# MovuinoHealthBandV0_2_4-EC.net
KiCad netlist of a schematic drawn in EAGLE
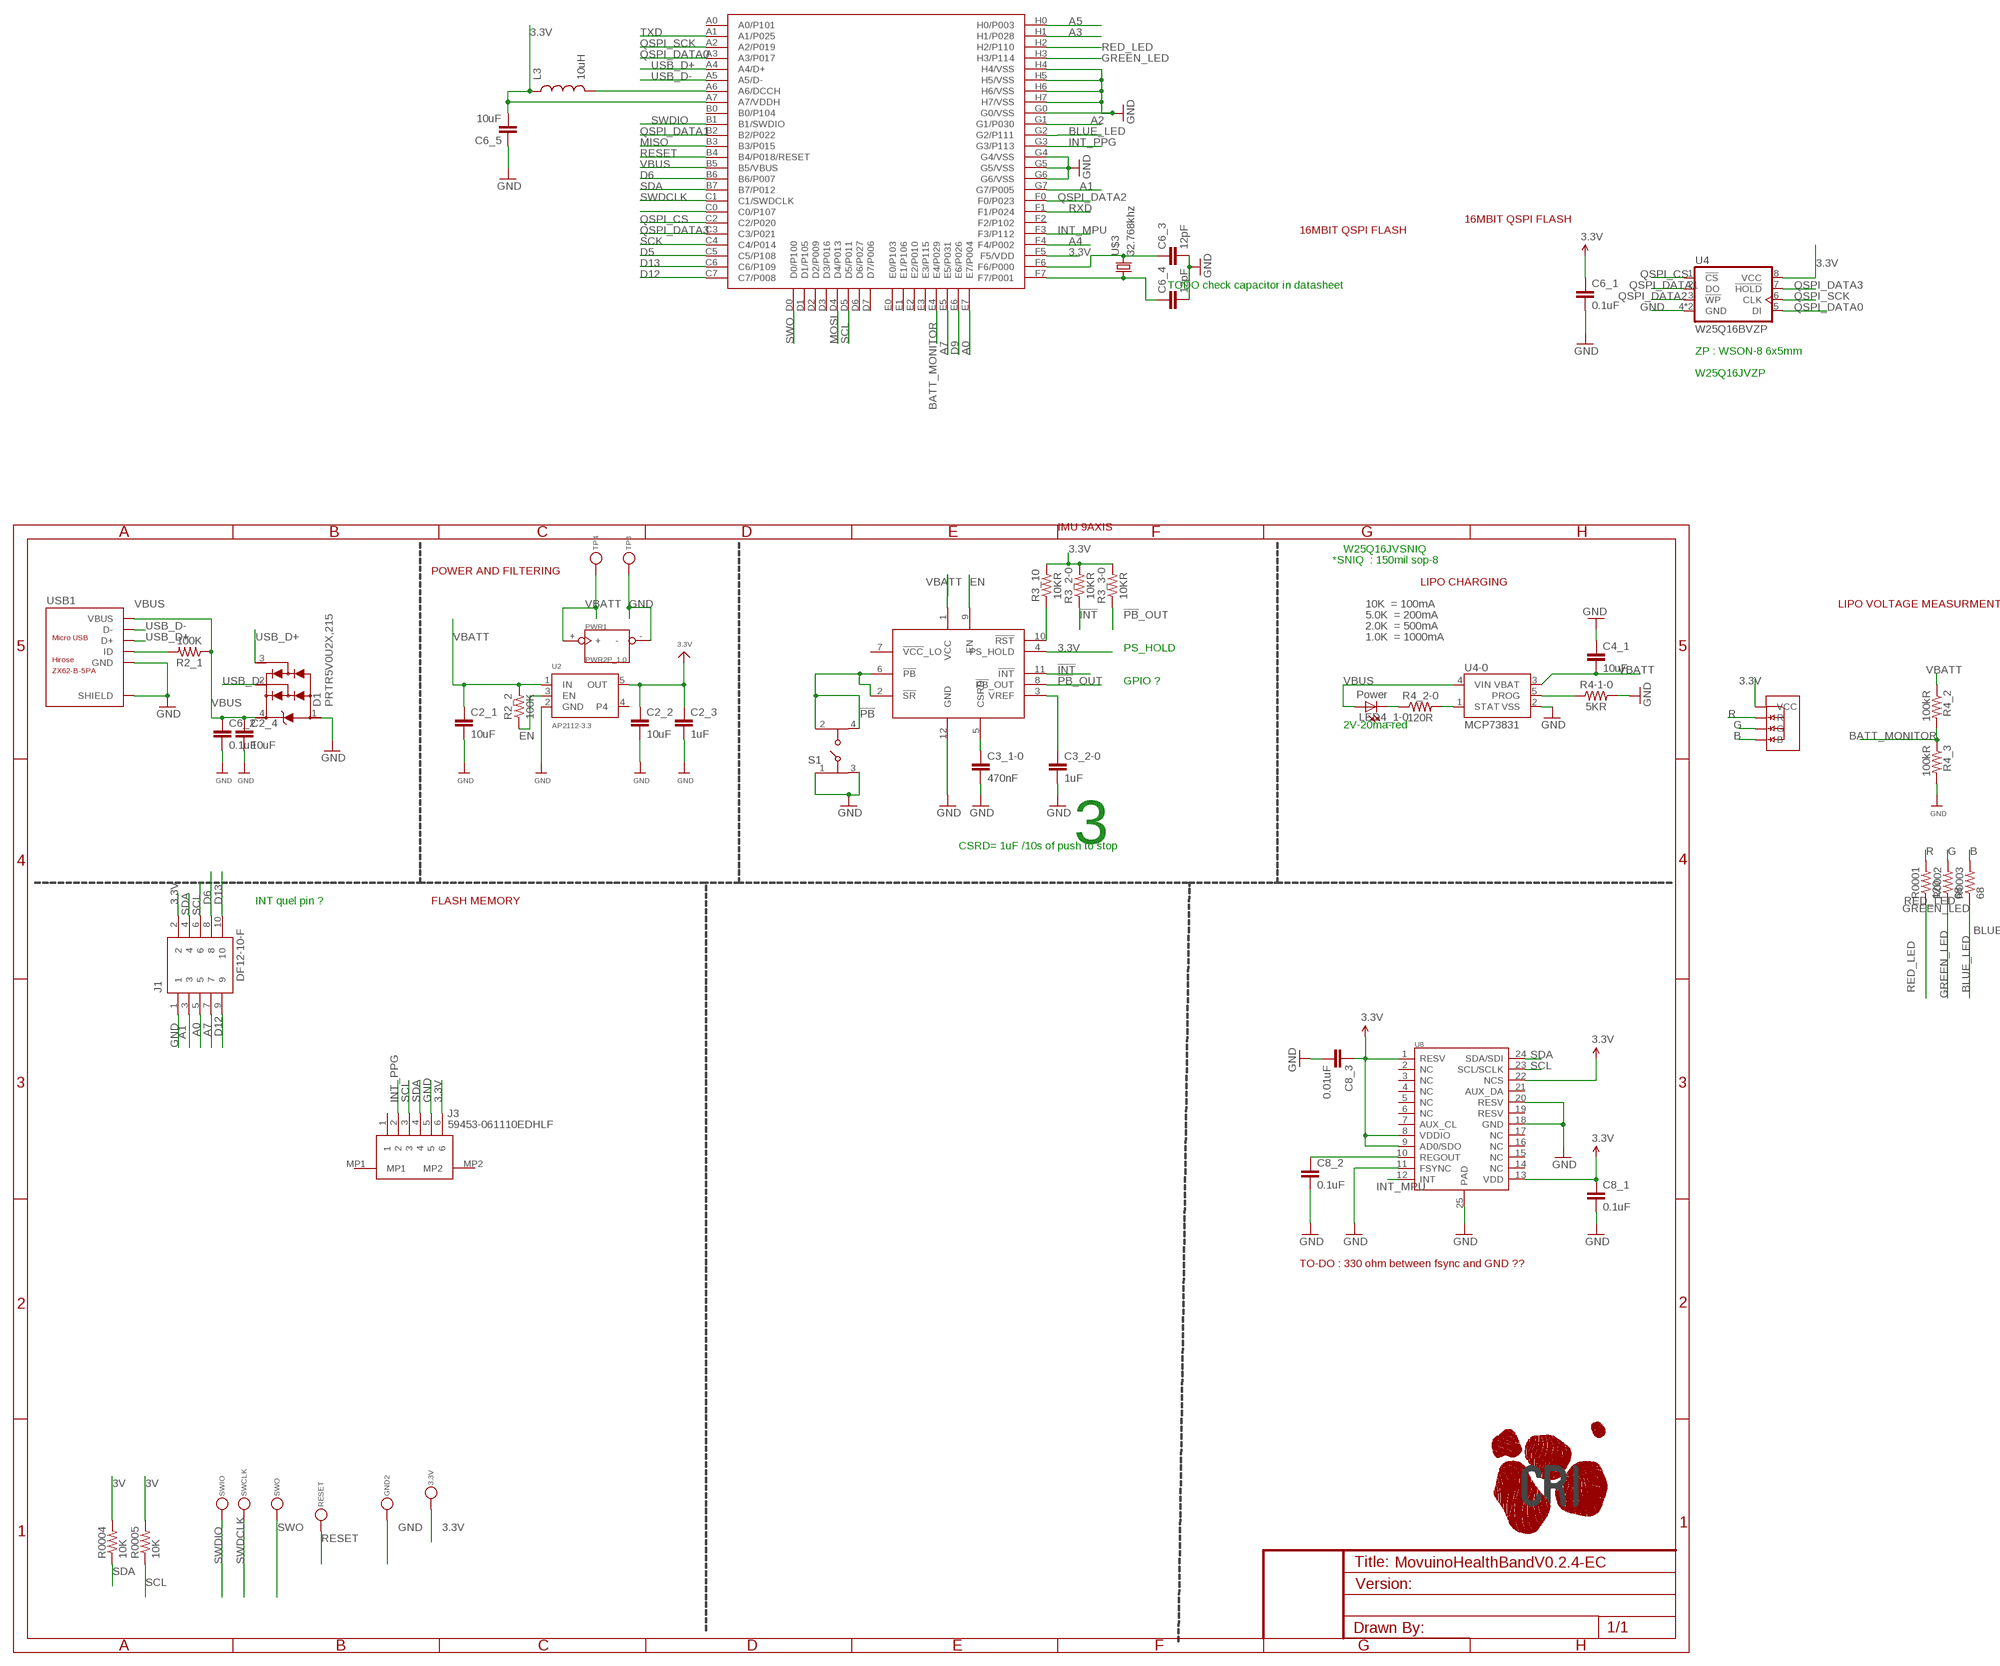
[diagram p0: schematic, sheet 1, part 1 of 2]
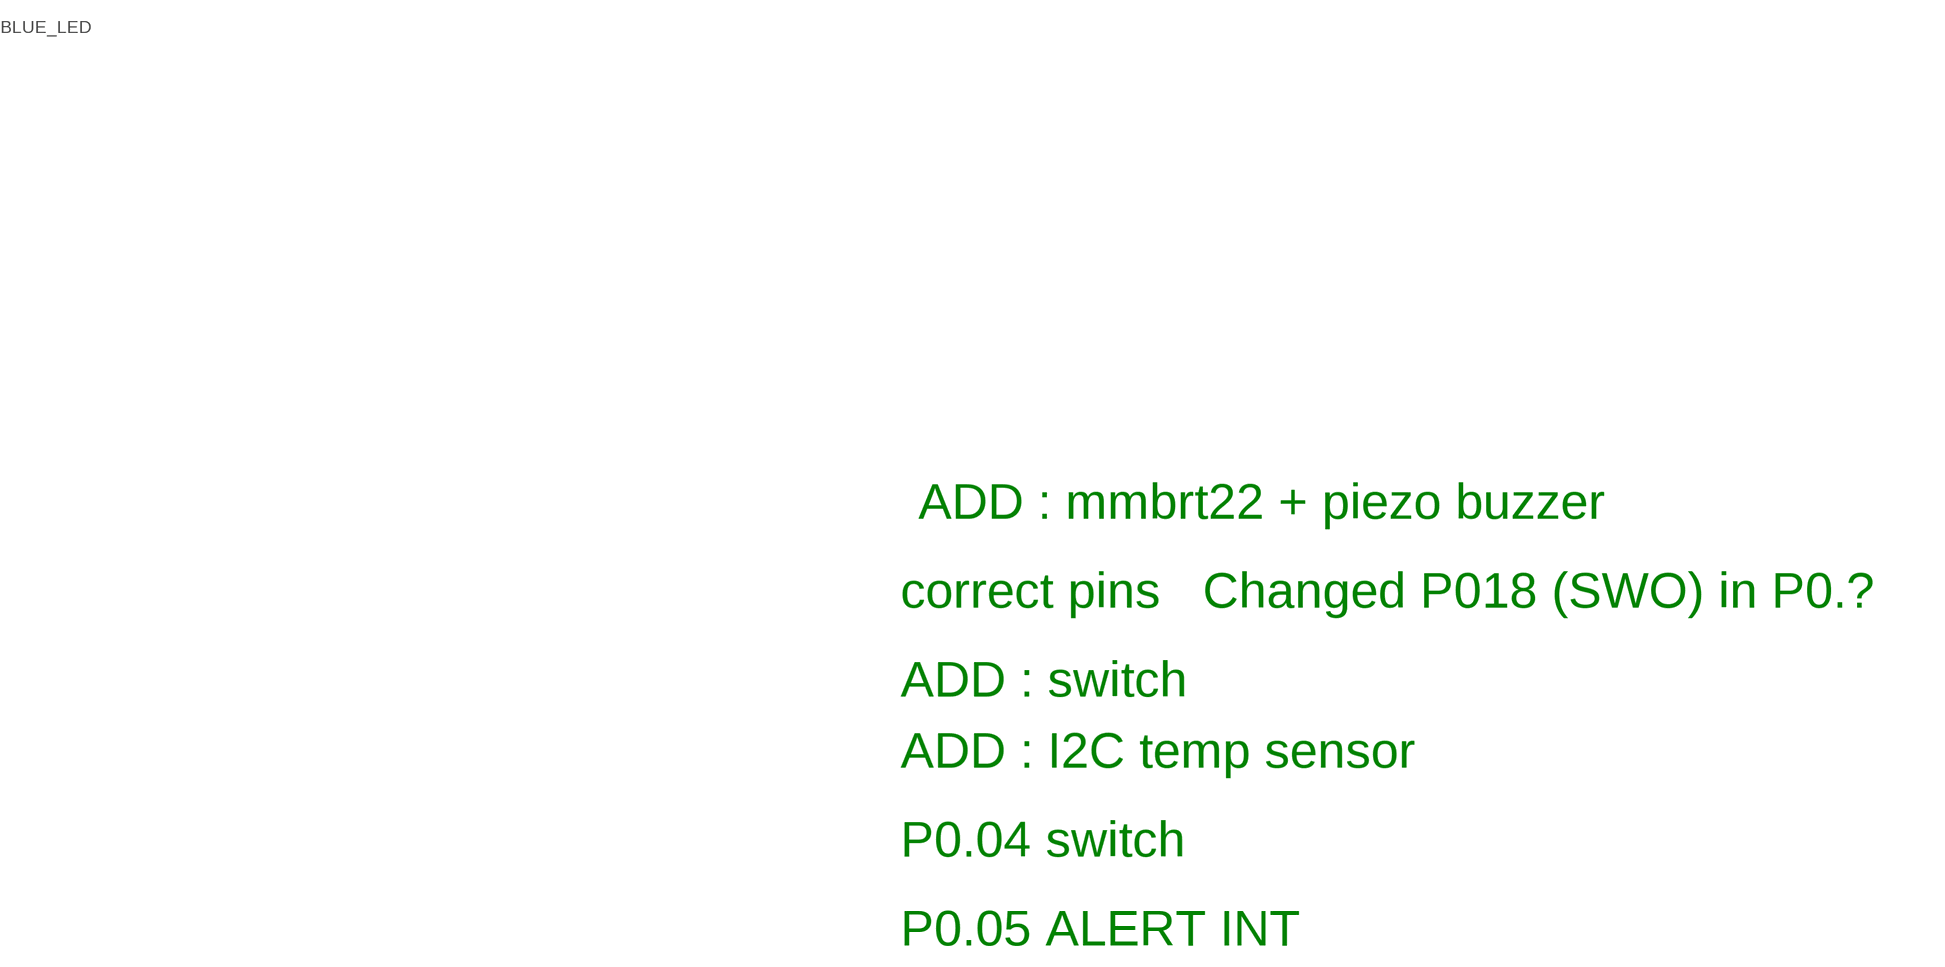
[diagram p1: schematic, sheet 1, part 2 of 2]

(export (version "E")
  (design (tool "Eeschema 10.0.6"))
  (components
    (comp (ref "3.3V")
      (value "TESTPOINTROUND1MM")
      (footprint "eagle-import:TESTPOINT_ROUND_1MM")
      (libsource (lib "eagle-import") (part "TESTPOINTROUND1MM"))
    )
    (comp (ref "C2_1")
      (value "10uF")
      (footprint "eagle-import:0402-CAP-SMALL-TDOCU")
      (libsource (lib "eagle-import") (part "CAP0402-CAP-SMALL-TDOCU"))
    )
    (comp (ref "C2_2")
      (value "10uF")
      (footprint "eagle-import:0402-CAP-SMALL-TDOCU")
      (libsource (lib "eagle-import") (part "CAP0402-CAP-SMALL-TDOCU"))
    )
    (comp (ref "C2_3")
      (value "1uF")
      (footprint "eagle-import:0402-CAP-SMALL-TDOCU")
      (libsource (lib "eagle-import") (part "CAP0402-CAP-SMALL-TDOCU"))
    )
    (comp (ref "C2_4")
      (value "10uF")
      (footprint "eagle-import:0402-CAP-SMALL-TDOCU")
      (libsource (lib "eagle-import") (part "CAP0402-CAP-SMALL-TDOCU"))
    )
    (comp (ref "C3_1-0")
      (value "470nF")
      (footprint "eagle-import:0402-CAP")
      (fields
        (field (name "MF") "Murata Electronics")
        (field (name "MPN") "GRM155R61A105KE15D")
        (field (name "TOLERANCE") "10%")
      )
      (libsource (lib "eagle-import") (part "CAP0402-1UF"))
    )
    (comp (ref "C3_2-0")
      (value "1uF")
      (footprint "eagle-import:0402-CAP")
      (fields
        (field (name "MF") "Murata Electronics")
        (field (name "MPN") "GRM155R61A105KE15D")
        (field (name "TOLERANCE") "10%")
      )
      (libsource (lib "eagle-import") (part "CAP0402-1UF"))
    )
    (comp (ref "C4_1")
      (value "10uF")
      (footprint "eagle-import:0402-CAP-SMALL-TDOCU")
      (libsource (lib "eagle-import") (part "CAP0402-CAP-SMALL-TDOCU"))
    )
    (comp (ref "C6_1")
      (value "0.1uF")
      (footprint "eagle-import:0402-CAP-SMALL-TDOCU")
      (libsource (lib "eagle-import") (part "CAP0402-CAP-SMALL-TDOCU"))
    )
    (comp (ref "C6_2")
      (value "0.1uF")
      (footprint "eagle-import:0402-CAP-SMALL-TDOCU")
      (libsource (lib "eagle-import") (part "CAP0402-CAP-SMALL-TDOCU"))
    )
    (comp (ref "C6_3")
      (value "12pF")
      (footprint "eagle-import:0402-CAP-SMALL-TDOCU")
      (libsource (lib "eagle-import") (part "CAP0402-CAP-SMALL-TDOCU"))
    )
    (comp (ref "C6_4")
      (value "12pF")
      (footprint "eagle-import:0402-CAP-SMALL-TDOCU")
      (libsource (lib "eagle-import") (part "CAP0402-CAP-SMALL-TDOCU"))
    )
    (comp (ref "C6_5")
      (value "10uF")
      (footprint "eagle-import:0402-CAP-SMALL-TDOCU")
      (libsource (lib "eagle-import") (part "CAP0402-CAP-SMALL-TDOCU"))
    )
    (comp (ref "C8_1")
      (value "0.1uF")
      (footprint "eagle-import:0402-CAP-SMALL-TDOCU")
      (libsource (lib "eagle-import") (part "CAP0402-CAP-SMALL-TDOCU"))
    )
    (comp (ref "C8_2")
      (value "0.1uF")
      (footprint "eagle-import:0402-CAP-SMALL-TDOCU")
      (libsource (lib "eagle-import") (part "CAP0402-CAP-SMALL-TDOCU"))
    )
    (comp (ref "C8_3")
      (value "0.01uF")
      (footprint "eagle-import:0402-CAP-SMALL-TDOCU")
      (libsource (lib "eagle-import") (part "CAP0402-CAP-SMALL-TDOCU"))
    )
    (comp (ref "D1")
      (value "PRTR5V0U2X,215")
      (footprint "eagle-import:SOT143B")
      (fields (field (name "MF") "Nexperia USA"))
      (libsource (lib "eagle-import") (part "PRTR5V0U2X,215"))
    )
    (comp (ref "GND2")
      (value "TESTPOINTROUND1MM")
      (footprint "eagle-import:TESTPOINT_ROUND_1MM")
      (libsource (lib "eagle-import") (part "TESTPOINTROUND1MM"))
    )
    (comp (ref "J1")
      (value "DF12-10-F")
      (footprint "eagle-import:DF12-10-DP")
      (fields (field (name "MF") "Hirose") (field (name "MPN") "DF12E(3.0)-10DP-0.5V(81)"))
      (libsource (lib "eagle-import") (part "DF12-10-F"))
    )
    (comp (ref "J3")
      (value "59453-061110EDHLF")
      (footprint "eagle-import:59453061110EDHLF")
      (libsource (lib "eagle-import") (part "59453-061110EDHLF"))
    )
    (comp (ref "L3")
      (value "10uH")
      (footprint "eagle-import:C0402")
      (libsource (lib "eagle-import") (part "INDUCTOR0402"))
    )
    (comp (ref "LED4_1-0")
      (value "Power")
      (footprint "eagle-import:LED-0603")
      (fields (field (name "MF") "OSRAM Opto Semiconductors") (field (name "MPN") "LS Q976-NR-1"))
      (libsource (lib "eagle-import") (part "LED0603-RED-STD"))
    )
    (comp (ref "PWR1")
      (value "PWR2P_1.0")
      (footprint "eagle-import:PWR2P_1.0")
      (fields (field (name "MF") "JST") (field (name "MPN") "SM02B-SRSS-TB(LFSN)"))
      (libsource (lib "eagle-import") (part "PWR2P_1.0"))
    )
    (comp (ref "R0001")
      (value "120")
      (footprint "eagle-import:0402-RES")
      (fields
        (field (name "MF") "TE Connectivity")
        (field (name "MPN") "CRG0402F10K")
        (field (name "TOLERANCE") "1%")
      )
      (libsource (lib "eagle-import") (part "RESISTOR0402-10K"))
    )
    (comp (ref "R0002")
      (value "68")
      (footprint "eagle-import:0402-RES")
      (fields
        (field (name "MF") "TE Connectivity")
        (field (name "MPN") "CRG0402F10K")
        (field (name "TOLERANCE") "1%")
      )
      (libsource (lib "eagle-import") (part "RESISTOR0402-10K"))
    )
    (comp (ref "R2_1")
      (value "100K")
      (footprint "eagle-import:R0402-SMALL-TDOCU")
      (libsource (lib "eagle-import") (part "RESISTORR0402-SMALL-TDOCU"))
    )
    (comp (ref "R2_2")
      (value "100K")
      (footprint "eagle-import:R0402-SMALL-TDOCU")
      (libsource (lib "eagle-import") (part "RESISTORR0402-SMALL-TDOCU"))
    )
    (comp (ref "R0003")
      (value "68")
      (footprint "eagle-import:0402-RES")
      (fields
        (field (name "MF") "TE Connectivity")
        (field (name "MPN") "CRG0402F10K")
        (field (name "TOLERANCE") "1%")
      )
      (libsource (lib "eagle-import") (part "RESISTOR0402-10K"))
    )
    (comp (ref "R3_2-0")
      (value "10KR")
      (footprint "eagle-import:R0402-SMALL-TDOCU")
      (libsource (lib "eagle-import") (part "RESISTORR0402-SMALL-TDOCU"))
    )
    (comp (ref "R3_3-0")
      (value "10KR")
      (footprint "eagle-import:R0402-SMALL-TDOCU")
      (libsource (lib "eagle-import") (part "RESISTORR0402-SMALL-TDOCU"))
    )
    (comp (ref "R3_10")
      (value "10KR")
      (footprint "eagle-import:R0402-SMALL-TDOCU")
      (libsource (lib "eagle-import") (part "RESISTORR0402-SMALL-TDOCU"))
    )
    (comp (ref "R0004")
      (value "10K")
      (footprint "eagle-import:0402-RES")
      (fields
        (field (name "MF") "TE Connectivity")
        (field (name "MPN") "CRG0402F10K")
        (field (name "TOLERANCE") "1%")
      )
      (libsource (lib "eagle-import") (part "RESISTOR0402-10K"))
    )
    (comp (ref "R4-1-0")
      (value "5KR")
      (footprint "eagle-import:R0402-SMALL-TDOCU")
      (libsource (lib "eagle-import") (part "RESISTORR0402-SMALL-TDOCU"))
    )
    (comp (ref "R4_2")
      (value "100kR")
      (footprint "eagle-import:0402-RES")
      (fields
        (field (name "MF") "TE Connectivity")
        (field (name "MPN") "CRG0402F10K")
        (field (name "TOLERANCE") "1%")
      )
      (libsource (lib "eagle-import") (part "RESISTOR0402-10K"))
    )
    (comp (ref "R4_2-0")
      (value "120R")
      (footprint "eagle-import:R0402-SMALL-TDOCU")
      (libsource (lib "eagle-import") (part "RESISTORR0402-SMALL-TDOCU"))
    )
    (comp (ref "R4_3")
      (value "100kR")
      (footprint "eagle-import:0402-RES")
      (fields
        (field (name "MF") "TE Connectivity")
        (field (name "MPN") "CRG0402F10K")
        (field (name "TOLERANCE") "1%")
      )
      (libsource (lib "eagle-import") (part "RESISTOR0402-10K"))
    )
    (comp (ref "R0005")
      (value "10K")
      (footprint "eagle-import:0402-RES")
      (fields
        (field (name "MF") "TE Connectivity")
        (field (name "MPN") "CRG0402F10K")
        (field (name "TOLERANCE") "1%")
      )
      (libsource (lib "eagle-import") (part "RESISTOR0402-10K"))
    )
    (comp (ref "RESET")
      (value "TESTPOINTROUND1MM")
      (footprint "eagle-import:TESTPOINT_ROUND_1MM")
      (libsource (lib "eagle-import") (part "TESTPOINTROUND1MM"))
    )
    (comp (ref "S1")
      (value "434331045822")
      (footprint "eagle-import:434331045822")
      (libsource (lib "eagle-import") (part "434331045822"))
    )
    (comp (ref "SWCLK")
      (value "TESTPOINTROUND1MM")
      (footprint "eagle-import:TESTPOINT_ROUND_1MM")
      (libsource (lib "eagle-import") (part "TESTPOINTROUND1MM"))
    )
    (comp (ref "SWIO")
      (value "TESTPOINTROUND1MM")
      (footprint "eagle-import:TESTPOINT_ROUND_1MM")
      (libsource (lib "eagle-import") (part "TESTPOINTROUND1MM"))
    )
    (comp (ref "SWO")
      (value "TESTPOINTROUND1MM")
      (footprint "eagle-import:TESTPOINT_ROUND_1MM")
      (libsource (lib "eagle-import") (part "TESTPOINTROUND1MM"))
    )
    (comp (ref "TP3")
      (value "TESTPOINT1X1.5MM_NOCREAM_NOSILK")
      (footprint "eagle-import:PAD-1X1.5_NOSILK")
      (libsource (lib "eagle-import") (part "TESTPOINT1X1.5MM_NOCREAM_NOSILK"))
    )
    (comp (ref "TP4")
      (value "TESTPOINT1X1.5MM_NOCREAM_NOSILK")
      (footprint "eagle-import:PAD-1X1.5_NOSILK")
      (libsource (lib "eagle-import") (part "TESTPOINT1X1.5MM_NOCREAM_NOSILK"))
    )
    (comp (ref "U$2")
      (value "LOGO-CRI-NEW-110MM-BOTTOM-SILK")
      (footprint "eagle-import:LOGO_CRI-NEW-BMP10MM-BOTTOM")
      (libsource (lib "eagle-import") (part "LOGO-CRI-NEW-110MM-BOTTOM-SILK"))
    )
    (comp (ref "U$3")
      (value "32.768khz")
      (footprint "eagle-import:CRYSTAL-SMD-2X1.2-ABS06")
      (libsource (lib "eagle-import") (part "CRYSTAL-NOGND"))
    )
    (comp (ref "U$24")
      (value "LRTB_R48G")
      (footprint "eagle-import:LRTB_R48G")
      (fields (field (name "MF") "Osram Opto Semiconductors") (field (name "MPN") "LRTBR48G"))
      (libsource (lib "eagle-import") (part "LRTB_R48G"))
    )
    (comp (ref "U2")
      (value "AP2112-3.3")
      (footprint "eagle-import:SOT23-5")
      (libsource (lib "eagle-import") (part "VREG_SOT23-5"))
    )
    (comp (ref "U3")
      (value "BC840")
      (footprint "eagle-import:BC840")
      (libsource (lib "eagle-import") (part "BC840"))
    )
    (comp (ref "U3-0")
      (value "STM6601")
      (footprint "eagle-import:TDFN12")
      (libsource (lib "eagle-import") (part "STM6601"))
    )
    (comp (ref "U4")
      (value "W25Q16BVZP")
      (footprint "eagle-import:WSON8")
      (libsource (lib "eagle-import") (part "W25Q16BVZP"))
    )
    (comp (ref "U4-0")
      (value "MCP73831")
      (footprint "eagle-import:SOT23-5")
      (fields (field (name "MF") "Microchip") (field (name "MPN") "MCP73831T-2ACI/OT"))
      (libsource (lib "eagle-import") (part "MCP73831"))
    )
    (comp (ref "U8")
      (value "MPU-9250")
      (footprint "eagle-import:LEAD-QFN24")
      (fields (field (name "MF") "InvenSense"))
      (libsource (lib "eagle-import") (part "MPU-9250"))
    )
    (comp (ref "USB1")
      (value "MICRO-USB-SMD(ZX62-B-5PA)TB1")
      (footprint "eagle-import:MICRO-USB5+6P-SMD-0.65-AB-TB")
      (libsource (lib "eagle-import") (part "MICRO-USB-SMD(ZX62-B-5PA)TB1"))
    )
  )
  (nets
    (net (code "1") (name "/3V") (class "Default")
      (node (ref "R0004") (pin "2") (pinfunction "2_2") (pintype "passive"))
      (node (ref "R0005") (pin "2") (pinfunction "2_2") (pintype "passive"))
    )
    (net (code "2") (name "/A0") (class "Default")
      (node (ref "J1") (pin "5") (pinfunction "5_5") (pintype "bidirectional"))
      (node (ref "U3") (pin "E7") (pinfunction "E7/P004_E7") (pintype "bidirectional"))
    )
    (net (code "3") (name "/A1") (class "Default")
      (node (ref "J1") (pin "3") (pinfunction "3_3") (pintype "bidirectional"))
      (node (ref "U3") (pin "G7") (pinfunction "G7/P005_G7") (pintype "bidirectional"))
    )
    (net (code "4") (name "/A2") (class "Default")
      (node (ref "U3") (pin "G1") (pinfunction "G1/P030_G1") (pintype "bidirectional"))
    )
    (net (code "5") (name "/A3") (class "Default")
      (node (ref "U3") (pin "H1") (pinfunction "H1/P028_H1") (pintype "bidirectional"))
    )
    (net (code "6") (name "/A4") (class "Default")
      (node (ref "U3") (pin "F4") (pinfunction "F4/P002_F4") (pintype "bidirectional"))
    )
    (net (code "7") (name "/A5") (class "Default")
      (node (ref "U3") (pin "H0") (pinfunction "H0/P003_H0") (pintype "bidirectional"))
    )
    (net (code "8") (name "/A7") (class "Default")
      (node (ref "J1") (pin "7") (pinfunction "7_7") (pintype "bidirectional"))
      (node (ref "U3") (pin "E5") (pinfunction "E5/P031_E5") (pintype "bidirectional"))
    )
    (net (code "9") (name "/B") (class "Default")
      (node (ref "R0003") (pin "2") (pinfunction "2_2") (pintype "passive"))
      (node (ref "U$24") (pin "4") (pinfunction "B_4") (pintype "bidirectional"))
    )
    (net (code "10") (name "/BATT_MONITOR") (class "Default")
      (node (ref "R4_2") (pin "2") (pinfunction "2_2") (pintype "passive"))
      (node (ref "R4_3") (pin "1") (pinfunction "1_1") (pintype "passive"))
      (node (ref "U3") (pin "E4") (pinfunction "E4/P029_E4") (pintype "bidirectional"))
    )
    (net (code "11") (name "/BLUE_LED") (class "Default")
      (node (ref "R0003") (pin "1") (pinfunction "1_1") (pintype "passive"))
      (node (ref "U3") (pin "G2") (pinfunction "G2/P111_G2") (pintype "bidirectional"))
    )
    (net (code "12") (name "/D5") (class "Default")
      (node (ref "U3") (pin "C5") (pinfunction "C5/P108_C5") (pintype "bidirectional"))
    )
    (net (code "13") (name "/D6") (class "Default")
      (node (ref "J1") (pin "8") (pinfunction "8_8") (pintype "bidirectional"))
      (node (ref "U3") (pin "B6") (pinfunction "B6/P007_B6") (pintype "bidirectional"))
    )
    (net (code "14") (name "/D9") (class "Default")
      (node (ref "U3") (pin "E6") (pinfunction "E6/P026_E6") (pintype "bidirectional"))
    )
    (net (code "15") (name "/D12") (class "Default")
      (node (ref "J1") (pin "9") (pinfunction "9_9") (pintype "bidirectional"))
      (node (ref "U3") (pin "C7") (pinfunction "C7/P008_C7") (pintype "bidirectional"))
    )
    (net (code "16") (name "/D13") (class "Default")
      (node (ref "J1") (pin "10") (pinfunction "10_10") (pintype "bidirectional"))
      (node (ref "U3") (pin "C6") (pinfunction "C6/P109_C6") (pintype "bidirectional"))
    )
    (net (code "17") (name "/EN") (class "Default")
      (node (ref "R2_2") (pin "1") (pinfunction "1_1") (pintype "passive"))
      (node (ref "U2") (pin "3") (pinfunction "EN_3") (pintype "input"))
      (node (ref "U3-0") (pin "9") (pinfunction "EN_9") (pintype "output"))
    )
    (net (code "18") (name "/G") (class "Default")
      (node (ref "R0002") (pin "2") (pinfunction "2_2") (pintype "passive"))
      (node (ref "U$24") (pin "3") (pinfunction "G_3") (pintype "bidirectional"))
    )
    (net (code "19") (name "/GREEN_LED") (class "Default")
      (node (ref "R0002") (pin "1") (pinfunction "1_1") (pintype "passive"))
      (node (ref "U3") (pin "H3") (pinfunction "H3/P114_H3") (pintype "bidirectional"))
    )
    (net (code "20") (name "/INT_MPU") (class "Default")
      (node (ref "U3") (pin "F3") (pinfunction "F3/P112_F3") (pintype "bidirectional"))
      (node (ref "U8") (pin "12") (pinfunction "INT_12") (pintype "bidirectional"))
    )
    (net (code "21") (name "/INT_PPG") (class "Default")
      (node (ref "J3") (pin "2") (pinfunction "2_2") (pintype "bidirectional"))
      (node (ref "U3") (pin "G3") (pinfunction "G3/P113_G3") (pintype "bidirectional"))
    )
    (net (code "22") (name "/MISO") (class "Default")
      (node (ref "U3") (pin "B3") (pinfunction "B3/P015_B3") (pintype "bidirectional"))
    )
    (net (code "23") (name "/MOSI") (class "Default")
      (node (ref "U3") (pin "D4") (pinfunction "D4/P013_D4") (pintype "bidirectional"))
    )
    (net (code "24") (name "/QSPI_CS") (class "Default")
      (node (ref "U3") (pin "C2") (pinfunction "C2/P020_C2") (pintype "bidirectional"))
      (node (ref "U4") (pin "1") (pinfunction "~{CS}_1") (pintype "input"))
    )
    (net (code "25") (name "/QSPI_DATA0") (class "Default")
      (node (ref "U3") (pin "A3") (pinfunction "A3/P017_A3") (pintype "bidirectional"))
      (node (ref "U4") (pin "5") (pinfunction "DI_5") (pintype "input"))
    )
    (net (code "26") (name "/QSPI_DATA1") (class "Default")
      (node (ref "U3") (pin "B2") (pinfunction "B2/P022_B2") (pintype "bidirectional"))
      (node (ref "U4") (pin "2") (pinfunction "DO_2") (pintype "output"))
    )
    (net (code "27") (name "/QSPI_DATA2") (class "Default")
      (node (ref "U3") (pin "F0") (pinfunction "F0/P023_F0") (pintype "bidirectional"))
      (node (ref "U4") (pin "3") (pinfunction "~{WP}_3") (pintype "input"))
    )
    (net (code "28") (name "/QSPI_DATA3") (class "Default")
      (node (ref "U3") (pin "C3") (pinfunction "C3/P021_C3") (pintype "bidirectional"))
      (node (ref "U4") (pin "7") (pinfunction "~{HOLD}_7") (pintype "input"))
    )
    (net (code "29") (name "/QSPI_SCK") (class "Default")
      (node (ref "U3") (pin "A2") (pinfunction "A2/P019_A2") (pintype "bidirectional"))
      (node (ref "U4") (pin "6") (pinfunction "CLK_6") (pintype "input"))
    )
    (net (code "30") (name "/R") (class "Default")
      (node (ref "R0001") (pin "2") (pinfunction "2_2") (pintype "passive"))
      (node (ref "U$24") (pin "2") (pinfunction "R_2") (pintype "bidirectional"))
    )
    (net (code "31") (name "/RED_LED") (class "Default")
      (node (ref "R0001") (pin "1") (pinfunction "1_1") (pintype "passive"))
      (node (ref "U3") (pin "H2") (pinfunction "H2/P110_H2") (pintype "bidirectional"))
    )
    (net (code "32") (name "/RESET") (class "Default")
      (node (ref "RESET") (pin "P$1") (pinfunction "P$1_P$1") (pintype "bidirectional"))
      (node (ref "U3") (pin "B4") (pinfunction "B4/P018/RESET_B4") (pintype "bidirectional"))
    )
    (net (code "33") (name "/RXD") (class "Default")
      (node (ref "U3") (pin "F1") (pinfunction "F1/P024_F1") (pintype "bidirectional"))
    )
    (net (code "34") (name "/SCK") (class "Default")
      (node (ref "U3") (pin "C4") (pinfunction "C4/P014_C4") (pintype "bidirectional"))
    )
    (net (code "35") (name "/SCL") (class "Default")
      (node (ref "J1") (pin "6") (pinfunction "6_6") (pintype "bidirectional"))
      (node (ref "J3") (pin "3") (pinfunction "3_3") (pintype "bidirectional"))
      (node (ref "R0005") (pin "1") (pinfunction "1_1") (pintype "passive"))
      (node (ref "U3") (pin "D5") (pinfunction "D5/P011_D5") (pintype "bidirectional"))
      (node (ref "U8") (pin "23") (pinfunction "SCL/SCLK_23") (pintype "bidirectional"))
    )
    (net (code "36") (name "/SDA") (class "Default")
      (node (ref "J1") (pin "4") (pinfunction "4_4") (pintype "bidirectional"))
      (node (ref "J3") (pin "4") (pinfunction "4_4") (pintype "bidirectional"))
      (node (ref "R0004") (pin "1") (pinfunction "1_1") (pintype "passive"))
      (node (ref "U3") (pin "B7") (pinfunction "B7/P012_B7") (pintype "bidirectional"))
      (node (ref "U8") (pin "24") (pinfunction "SDA/SDI_24") (pintype "bidirectional"))
    )
    (net (code "37") (name "/SWDCLK") (class "Default")
      (node (ref "SWCLK") (pin "P$1") (pinfunction "P$1_P$1") (pintype "bidirectional"))
      (node (ref "U3") (pin "C1") (pinfunction "C1/SWDCLK_C1") (pintype "bidirectional"))
    )
    (net (code "38") (name "/SWDIO") (class "Default")
      (node (ref "SWIO") (pin "P$1") (pinfunction "P$1_P$1") (pintype "bidirectional"))
      (node (ref "U3") (pin "B1") (pinfunction "B1/SWDIO_B1") (pintype "bidirectional"))
    )
    (net (code "39") (name "/SWO") (class "Default")
      (node (ref "SWO") (pin "P$1") (pinfunction "P$1_P$1") (pintype "bidirectional"))
      (node (ref "U3") (pin "D0") (pinfunction "D0/P100_D0") (pintype "bidirectional"))
    )
    (net (code "40") (name "/TXD") (class "Default")
      (node (ref "U3") (pin "A1") (pinfunction "A1/P025_A1") (pintype "bidirectional"))
    )
    (net (code "41") (name "/USB_D+") (class "Default")
      (node (ref "D1") (pin "3") (pinfunction "P$3_3") (pintype "passive"))
      (node (ref "U3") (pin "A4") (pinfunction "A4/D+_A4") (pintype "bidirectional"))
      (node (ref "USB1") (pin "3") (pinfunction "D+_3") (pintype "bidirectional"))
    )
    (net (code "42") (name "/USB_D-") (class "Default")
      (node (ref "D1") (pin "2") (pinfunction "P$2_2") (pintype "passive"))
      (node (ref "U3") (pin "A5") (pinfunction "A5/D-_A5") (pintype "bidirectional"))
      (node (ref "USB1") (pin "2") (pinfunction "D-_2") (pintype "bidirectional"))
    )
    (net (code "43") (name "/VBATT") (class "Default")
      (node (ref "C2_1") (pin "1") (pinfunction "1_1") (pintype "passive"))
      (node (ref "C4_1") (pin "2") (pinfunction "2_2") (pintype "passive"))
      (node (ref "PWR1") (pin "+") (pinfunction "+_+") (pintype "bidirectional"))
      (node (ref "R2_2") (pin "2") (pinfunction "2_2") (pintype "passive"))
      (node (ref "R4_2") (pin "1") (pinfunction "1_1") (pintype "passive"))
      (node (ref "TP4") (pin "P$1") (pinfunction "P$1_P$1") (pintype "bidirectional"))
      (node (ref "U2") (pin "1") (pinfunction "IN_1") (pintype "power_in"))
      (node (ref "U3-0") (pin "1") (pinfunction "VCC_1") (pintype "power_in"))
      (node (ref "U4-0") (pin "3") (pinfunction "VBAT_3") (pintype "power_in"))
    )
    (net (code "44") (name "/VBUS") (class "Default")
      (node (ref "C2_4") (pin "1") (pinfunction "1_1") (pintype "passive"))
      (node (ref "C6_2") (pin "1") (pinfunction "1_1") (pintype "passive"))
      (node (ref "D1") (pin "4") (pinfunction "P$4_4") (pintype "passive"))
      (node (ref "LED4_1-0") (pin "A") (pinfunction "A_A") (pintype "passive"))
      (node (ref "R2_1") (pin "1") (pinfunction "1_1") (pintype "passive"))
      (node (ref "U3") (pin "B5") (pinfunction "B5/VBUS_B5") (pintype "bidirectional"))
      (node (ref "U4-0") (pin "4") (pinfunction "VIN_4") (pintype "power_in"))
      (node (ref "USB1") (pin "1") (pinfunction "VBUS_1") (pintype "power_in"))
    )
    (net (code "45") (name "/~{INT}") (class "Default")
      (node (ref "R3_2-0") (pin "1") (pinfunction "1_1") (pintype "passive"))
      (node (ref "U3-0") (pin "11") (pinfunction "~{INT}_11") (pintype "output"))
    )
    (net (code "46") (name "/~{PB}") (class "Default")
      (node (ref "S1") (pin "2") (pinfunction "4_2") (pintype "passive"))
      (node (ref "S1") (pin "4") (pinfunction "2_4") (pintype "passive"))
      (node (ref "U3-0") (pin "2") (pinfunction "~{SR}_2") (pintype "bidirectional"))
      (node (ref "U3-0") (pin "6") (pinfunction "~{PB}_6") (pintype "bidirectional"))
    )
    (net (code "47") (name "/~{PB}_OUT") (class "Default")
      (node (ref "R3_3-0") (pin "1") (pinfunction "1_1") (pintype "passive"))
      (node (ref "U3-0") (pin "8") (pinfunction "~{PB}_OUT_8") (pintype "output"))
    )
    (net (code "48") (name "3.3V") (class "Default")
      (node (ref "3.3V") (pin "P$1") (pinfunction "P$1_P$1") (pintype "bidirectional"))
      (node (ref "C2_2") (pin "1") (pinfunction "1_1") (pintype "passive"))
      (node (ref "C2_3") (pin "1") (pinfunction "1_1") (pintype "passive"))
      (node (ref "C6_1") (pin "1") (pinfunction "1_1") (pintype "passive"))
      (node (ref "C6_5") (pin "2") (pinfunction "2_2") (pintype "passive"))
      (node (ref "C8_1") (pin "1") (pinfunction "1_1") (pintype "passive"))
      (node (ref "C8_3") (pin "1") (pinfunction "1_1") (pintype "passive"))
      (node (ref "J1") (pin "2") (pinfunction "2_2") (pintype "bidirectional"))
      (node (ref "J3") (pin "6") (pinfunction "6_6") (pintype "bidirectional"))
      (node (ref "L3") (pin "1") (pinfunction "1_1") (pintype "passive"))
      (node (ref "R3_10") (pin "2") (pinfunction "2_2") (pintype "passive"))
      (node (ref "R3_2-0") (pin "2") (pinfunction "2_2") (pintype "passive"))
      (node (ref "R3_3-0") (pin "2") (pinfunction "2_2") (pintype "passive"))
      (node (ref "U$24") (pin "1") (pinfunction "VCC_1") (pintype "input"))
      (node (ref "U2") (pin "5") (pinfunction "OUT_5") (pintype "power_in"))
      (node (ref "U3") (pin "A7") (pinfunction "A7/VDDH_A7") (pintype "bidirectional"))
      (node (ref "U3") (pin "F5") (pinfunction "F5/VDD_F5") (pintype "bidirectional"))
      (node (ref "U3-0") (pin "4") (pinfunction "PS_HOLD_4") (pintype "input"))
      (node (ref "U4") (pin "8") (pinfunction "VCC_8") (pintype "power_in"))
      (node (ref "U8") (pin "1") (pinfunction "RESV_1") (pintype "bidirectional"))
      (node (ref "U8") (pin "13") (pinfunction "VDD_13") (pintype "bidirectional"))
      (node (ref "U8") (pin "22") (pinfunction "NCS_22") (pintype "bidirectional"))
      (node (ref "U8") (pin "8") (pinfunction "VDDIO_8") (pintype "bidirectional"))
      (node (ref "U8") (pin "9") (pinfunction "AD0/SDO_9") (pintype "bidirectional"))
    )
    (net (code "49") (name "GND") (class "Default")
      (node (ref "C2_1") (pin "2") (pinfunction "2_2") (pintype "passive"))
      (node (ref "C2_2") (pin "2") (pinfunction "2_2") (pintype "passive"))
      (node (ref "C2_3") (pin "2") (pinfunction "2_2") (pintype "passive"))
      (node (ref "C2_4") (pin "2") (pinfunction "2_2") (pintype "passive"))
      (node (ref "C3_1-0") (pin "2") (pinfunction "2_2") (pintype "passive"))
      (node (ref "C3_2-0") (pin "2") (pinfunction "2_2") (pintype "passive"))
      (node (ref "C4_1") (pin "1") (pinfunction "1_1") (pintype "passive"))
      (node (ref "C6_1") (pin "2") (pinfunction "2_2") (pintype "passive"))
      (node (ref "C6_2") (pin "2") (pinfunction "2_2") (pintype "passive"))
      (node (ref "C6_3") (pin "2") (pinfunction "2_2") (pintype "passive"))
      (node (ref "C6_4") (pin "2") (pinfunction "2_2") (pintype "passive"))
      (node (ref "C6_5") (pin "1") (pinfunction "1_1") (pintype "passive"))
      (node (ref "C8_1") (pin "2") (pinfunction "2_2") (pintype "passive"))
      (node (ref "C8_2") (pin "2") (pinfunction "2_2") (pintype "passive"))
      (node (ref "C8_3") (pin "2") (pinfunction "2_2") (pintype "passive"))
      (node (ref "D1") (pin "1") (pinfunction "P$1_1") (pintype "passive"))
      (node (ref "GND2") (pin "P$1") (pinfunction "P$1_P$1") (pintype "bidirectional"))
      (node (ref "J1") (pin "1") (pinfunction "1_1") (pintype "bidirectional"))
      (node (ref "J3") (pin "5") (pinfunction "5_5") (pintype "bidirectional"))
      (node (ref "PWR1") (pin "-") (pinfunction "-_-") (pintype "bidirectional"))
      (node (ref "R4-1-0") (pin "2") (pinfunction "2_2") (pintype "passive"))
      (node (ref "R4_3") (pin "2") (pinfunction "2_2") (pintype "passive"))
      (node (ref "S1") (pin "1") (pinfunction "3_1") (pintype "passive"))
      (node (ref "S1") (pin "3") (pinfunction "1_3") (pintype "passive"))
      (node (ref "TP3") (pin "P$1") (pinfunction "P$1_P$1") (pintype "bidirectional"))
      (node (ref "U2") (pin "2") (pinfunction "GND_2") (pintype "power_in"))
      (node (ref "U3") (pin "G0") (pinfunction "G0/VSS_G0") (pintype "bidirectional"))
      (node (ref "U3") (pin "G4") (pinfunction "G4/VSS_G4") (pintype "bidirectional"))
      (node (ref "U3") (pin "G5") (pinfunction "G5/VSS_G5") (pintype "bidirectional"))
      (node (ref "U3") (pin "G6") (pinfunction "G6/VSS_G6") (pintype "bidirectional"))
      (node (ref "U3") (pin "H4") (pinfunction "H4/VSS_H4") (pintype "bidirectional"))
      (node (ref "U3") (pin "H5") (pinfunction "H5/VSS_H5") (pintype "bidirectional"))
      (node (ref "U3") (pin "H6") (pinfunction "H6/VSS_H6") (pintype "bidirectional"))
      (node (ref "U3") (pin "H7") (pinfunction "H7/VSS_H7") (pintype "bidirectional"))
      (node (ref "U3-0") (pin "12") (pinfunction "GND_12") (pintype "power_in"))
      (node (ref "U4") (pin "4") (pinfunction "GND_4") (pintype "power_in"))
      (node (ref "U4") (pin "9") (pinfunction "GND_9") (pintype "power_in"))
      (node (ref "U4-0") (pin "2") (pinfunction "VSS_2") (pintype "power_in"))
      (node (ref "U8") (pin "11") (pinfunction "FSYNC_11") (pintype "bidirectional"))
      (node (ref "U8") (pin "18") (pinfunction "GND_18") (pintype "bidirectional"))
      (node (ref "U8") (pin "20") (pinfunction "RESV_20") (pintype "bidirectional"))
      (node (ref "U8") (pin "25") (pinfunction "PAD_25") (pintype "bidirectional"))
      (node (ref "USB1") (pin "5") (pinfunction "GND_5") (pintype "power_in"))
      (node (ref "USB1") (pin "P$3") (pinfunction "SHIELD_P$3") (pintype "power_in"))
      (node (ref "USB1") (pin "P$4") (pinfunction "SHIELD_P$4") (pintype "power_in"))
      (node (ref "USB1") (pin "P1") (pinfunction "SHIELD_P1") (pintype "power_in"))
      (node (ref "USB1") (pin "P2") (pinfunction "SHIELD_P2") (pintype "power_in"))
      (node (ref "USB1") (pin "P5") (pinfunction "SHIELD_P5") (pintype "power_in"))
      (node (ref "USB1") (pin "P6") (pinfunction "SHIELD_P6") (pintype "power_in"))
    )
    (net (code "50") (name "Net-(LED4_1-0-PadC)") (class "Default")
      (node (ref "LED4_1-0") (pin "C") (pinfunction "C_C") (pintype "passive"))
      (node (ref "R4_2-0") (pin "1") (pinfunction "1_1") (pintype "passive"))
    )
    (net (code "51") (name "Net-(U$3-1)") (class "Default")
      (node (ref "C6_4") (pin "1") (pinfunction "1_1") (pintype "passive"))
      (node (ref "U$3") (pin "P$1") (pinfunction "1_P$1") (pintype "passive"))
      (node (ref "U3") (pin "F7") (pinfunction "F7/P001_F7") (pintype "bidirectional"))
    )
    (net (code "52") (name "Net-(U$3-2)") (class "Default")
      (node (ref "C6_3") (pin "1") (pinfunction "1_1") (pintype "passive"))
      (node (ref "U$3") (pin "P$2") (pinfunction "2_P$2") (pintype "passive"))
      (node (ref "U3") (pin "F6") (pinfunction "F6/P000_F6") (pintype "bidirectional"))
    )
    (net (code "53") (name "Net-(U3-0-CSRD)") (class "Default")
      (node (ref "C3_1-0") (pin "1") (pinfunction "1_1") (pintype "passive"))
      (node (ref "U3-0") (pin "5") (pinfunction "CSRD_5") (pintype "bidirectional"))
    )
    (net (code "54") (name "Net-(U3-0-VREF)") (class "Default")
      (node (ref "C3_2-0") (pin "1") (pinfunction "1_1") (pintype "passive"))
      (node (ref "U3-0") (pin "3") (pinfunction "VREF_3") (pintype "output"))
    )
    (net (code "55") (name "Net-(U3-0-~{RST})") (class "Default")
      (node (ref "R3_10") (pin "1") (pinfunction "1_1") (pintype "passive"))
      (node (ref "U3-0") (pin "10") (pinfunction "~{RST}_10") (pintype "output"))
    )
    (net (code "56") (name "Net-(U3-A6{slash}DCCH)") (class "Default")
      (node (ref "L3") (pin "2") (pinfunction "2_2") (pintype "passive"))
      (node (ref "U3") (pin "A6") (pinfunction "A6/DCCH_A6") (pintype "bidirectional"))
    )
    (net (code "57") (name "Net-(U4-0-PROG)") (class "Default")
      (node (ref "R4-1-0") (pin "1") (pinfunction "1_1") (pintype "passive"))
      (node (ref "U4-0") (pin "5") (pinfunction "PROG_5") (pintype "input"))
    )
    (net (code "58") (name "Net-(U4-0-STAT)") (class "Default")
      (node (ref "R4_2-0") (pin "2") (pinfunction "2_2") (pintype "passive"))
      (node (ref "U4-0") (pin "1") (pinfunction "STAT_1") (pintype "output"))
    )
    (net (code "59") (name "Net-(U8-REGOUT)") (class "Default")
      (node (ref "C8_2") (pin "1") (pinfunction "1_1") (pintype "passive"))
      (node (ref "U8") (pin "10") (pinfunction "REGOUT_10") (pintype "bidirectional"))
    )
    (net (code "60") (name "Net-(USB1-ID)") (class "Default")
      (node (ref "R2_1") (pin "2") (pinfunction "2_2") (pintype "passive"))
      (node (ref "USB1") (pin "4") (pinfunction "ID_4") (pintype "bidirectional"))
    )
    (net (code "61") (name "unconnected-(J3-Pad1)") (class "Default")
      (node (ref "J3") (pin "1") (pinfunction "1_1") (pintype "bidirectional"))
    )
    (net (code "62") (name "unconnected-(J3-PadMP1)") (class "Default")
      (node (ref "J3") (pin "MP1") (pinfunction "MP1_MP1") (pintype "bidirectional"))
    )
    (net (code "63") (name "unconnected-(J3-PadMP2)") (class "Default")
      (node (ref "J3") (pin "MP2") (pinfunction "MP2_MP2") (pintype "bidirectional"))
    )
    (net (code "64") (name "unconnected-(U2-P4-Pad4)") (class "Default")
      (node (ref "U2") (pin "4") (pinfunction "P4_4") (pintype "bidirectional"))
    )
    (net (code "65") (name "unconnected-(U3-0-~{VCC}_LO-Pad7)") (class "Default")
      (node (ref "U3-0") (pin "7") (pinfunction "~{VCC}_LO_7") (pintype "bidirectional"))
    )
    (net (code "66") (name "unconnected-(U3-A0{slash}P101-PadA0)") (class "Default")
      (node (ref "U3") (pin "A0") (pinfunction "A0/P101_A0") (pintype "bidirectional"))
    )
    (net (code "67") (name "unconnected-(U3-B0{slash}P104-PadB0)") (class "Default")
      (node (ref "U3") (pin "B0") (pinfunction "B0/P104_B0") (pintype "bidirectional"))
    )
    (net (code "68") (name "unconnected-(U3-C0{slash}P107-PadC0)") (class "Default")
      (node (ref "U3") (pin "C0") (pinfunction "C0/P107_C0") (pintype "bidirectional"))
    )
    (net (code "69") (name "unconnected-(U3-D1{slash}P105-PadD1)") (class "Default")
      (node (ref "U3") (pin "D1") (pinfunction "D1/P105_D1") (pintype "bidirectional"))
    )
    (net (code "70") (name "unconnected-(U3-D2{slash}P009-PadD2)") (class "Default")
      (node (ref "U3") (pin "D2") (pinfunction "D2/P009_D2") (pintype "bidirectional"))
    )
    (net (code "71") (name "unconnected-(U3-D3{slash}P016-PadD3)") (class "Default")
      (node (ref "U3") (pin "D3") (pinfunction "D3/P016_D3") (pintype "bidirectional"))
    )
    (net (code "72") (name "unconnected-(U3-D6{slash}P027-PadD6)") (class "Default")
      (node (ref "U3") (pin "D6") (pinfunction "D6/P027_D6") (pintype "bidirectional"))
    )
    (net (code "73") (name "unconnected-(U3-D7{slash}P006-PadD7)") (class "Default")
      (node (ref "U3") (pin "D7") (pinfunction "D7/P006_D7") (pintype "bidirectional"))
    )
    (net (code "74") (name "unconnected-(U3-E0{slash}P103-PadE0)") (class "Default")
      (node (ref "U3") (pin "E0") (pinfunction "E0/P103_E0") (pintype "bidirectional"))
    )
    (net (code "75") (name "unconnected-(U3-E1{slash}P106-PadE1)") (class "Default")
      (node (ref "U3") (pin "E1") (pinfunction "E1/P106_E1") (pintype "bidirectional"))
    )
    (net (code "76") (name "unconnected-(U3-E2{slash}P010-PadE2)") (class "Default")
      (node (ref "U3") (pin "E2") (pinfunction "E2/P010_E2") (pintype "bidirectional"))
    )
    (net (code "77") (name "unconnected-(U3-E3{slash}P115-PadE3)") (class "Default")
      (node (ref "U3") (pin "E3") (pinfunction "E3/P115_E3") (pintype "bidirectional"))
    )
    (net (code "78") (name "unconnected-(U3-F2{slash}P102-PadF2)") (class "Default")
      (node (ref "U3") (pin "F2") (pinfunction "F2/P102_F2") (pintype "bidirectional"))
    )
    (net (code "79") (name "unconnected-(U8-AUX_CL-Pad7)") (class "Default")
      (node (ref "U8") (pin "7") (pinfunction "AUX_CL_7") (pintype "bidirectional"))
    )
    (net (code "80") (name "unconnected-(U8-AUX_DA-Pad21)") (class "Default")
      (node (ref "U8") (pin "21") (pinfunction "AUX_DA_21") (pintype "bidirectional"))
    )
    (net (code "81") (name "unconnected-(U8-NC-Pad2)") (class "Default")
      (node (ref "U8") (pin "2") (pinfunction "NC_2") (pintype "bidirectional"))
    )
    (net (code "82") (name "unconnected-(U8-NC-Pad3)") (class "Default")
      (node (ref "U8") (pin "3") (pinfunction "NC_3") (pintype "bidirectional"))
    )
    (net (code "83") (name "unconnected-(U8-NC-Pad4)") (class "Default")
      (node (ref "U8") (pin "4") (pinfunction "NC_4") (pintype "bidirectional"))
    )
    (net (code "84") (name "unconnected-(U8-NC-Pad5)") (class "Default")
      (node (ref "U8") (pin "5") (pinfunction "NC_5") (pintype "bidirectional"))
    )
    (net (code "85") (name "unconnected-(U8-NC-Pad6)") (class "Default")
      (node (ref "U8") (pin "6") (pinfunction "NC_6") (pintype "bidirectional"))
    )
    (net (code "86") (name "unconnected-(U8-NC-Pad14)") (class "Default")
      (node (ref "U8") (pin "14") (pinfunction "NC_14") (pintype "bidirectional"))
    )
    (net (code "87") (name "unconnected-(U8-NC-Pad15)") (class "Default")
      (node (ref "U8") (pin "15") (pinfunction "NC_15") (pintype "bidirectional"))
    )
    (net (code "88") (name "unconnected-(U8-NC-Pad16)") (class "Default")
      (node (ref "U8") (pin "16") (pinfunction "NC_16") (pintype "bidirectional"))
    )
    (net (code "89") (name "unconnected-(U8-NC-Pad17)") (class "Default")
      (node (ref "U8") (pin "17") (pinfunction "NC_17") (pintype "bidirectional"))
    )
    (net (code "90") (name "unconnected-(U8-RESV-Pad19)") (class "Default")
      (node (ref "U8") (pin "19") (pinfunction "RESV_19") (pintype "bidirectional"))
    )
  )
)
